# CONNECTOR_A.net
KiCad netlist of a schematic drawn in Altium Designer
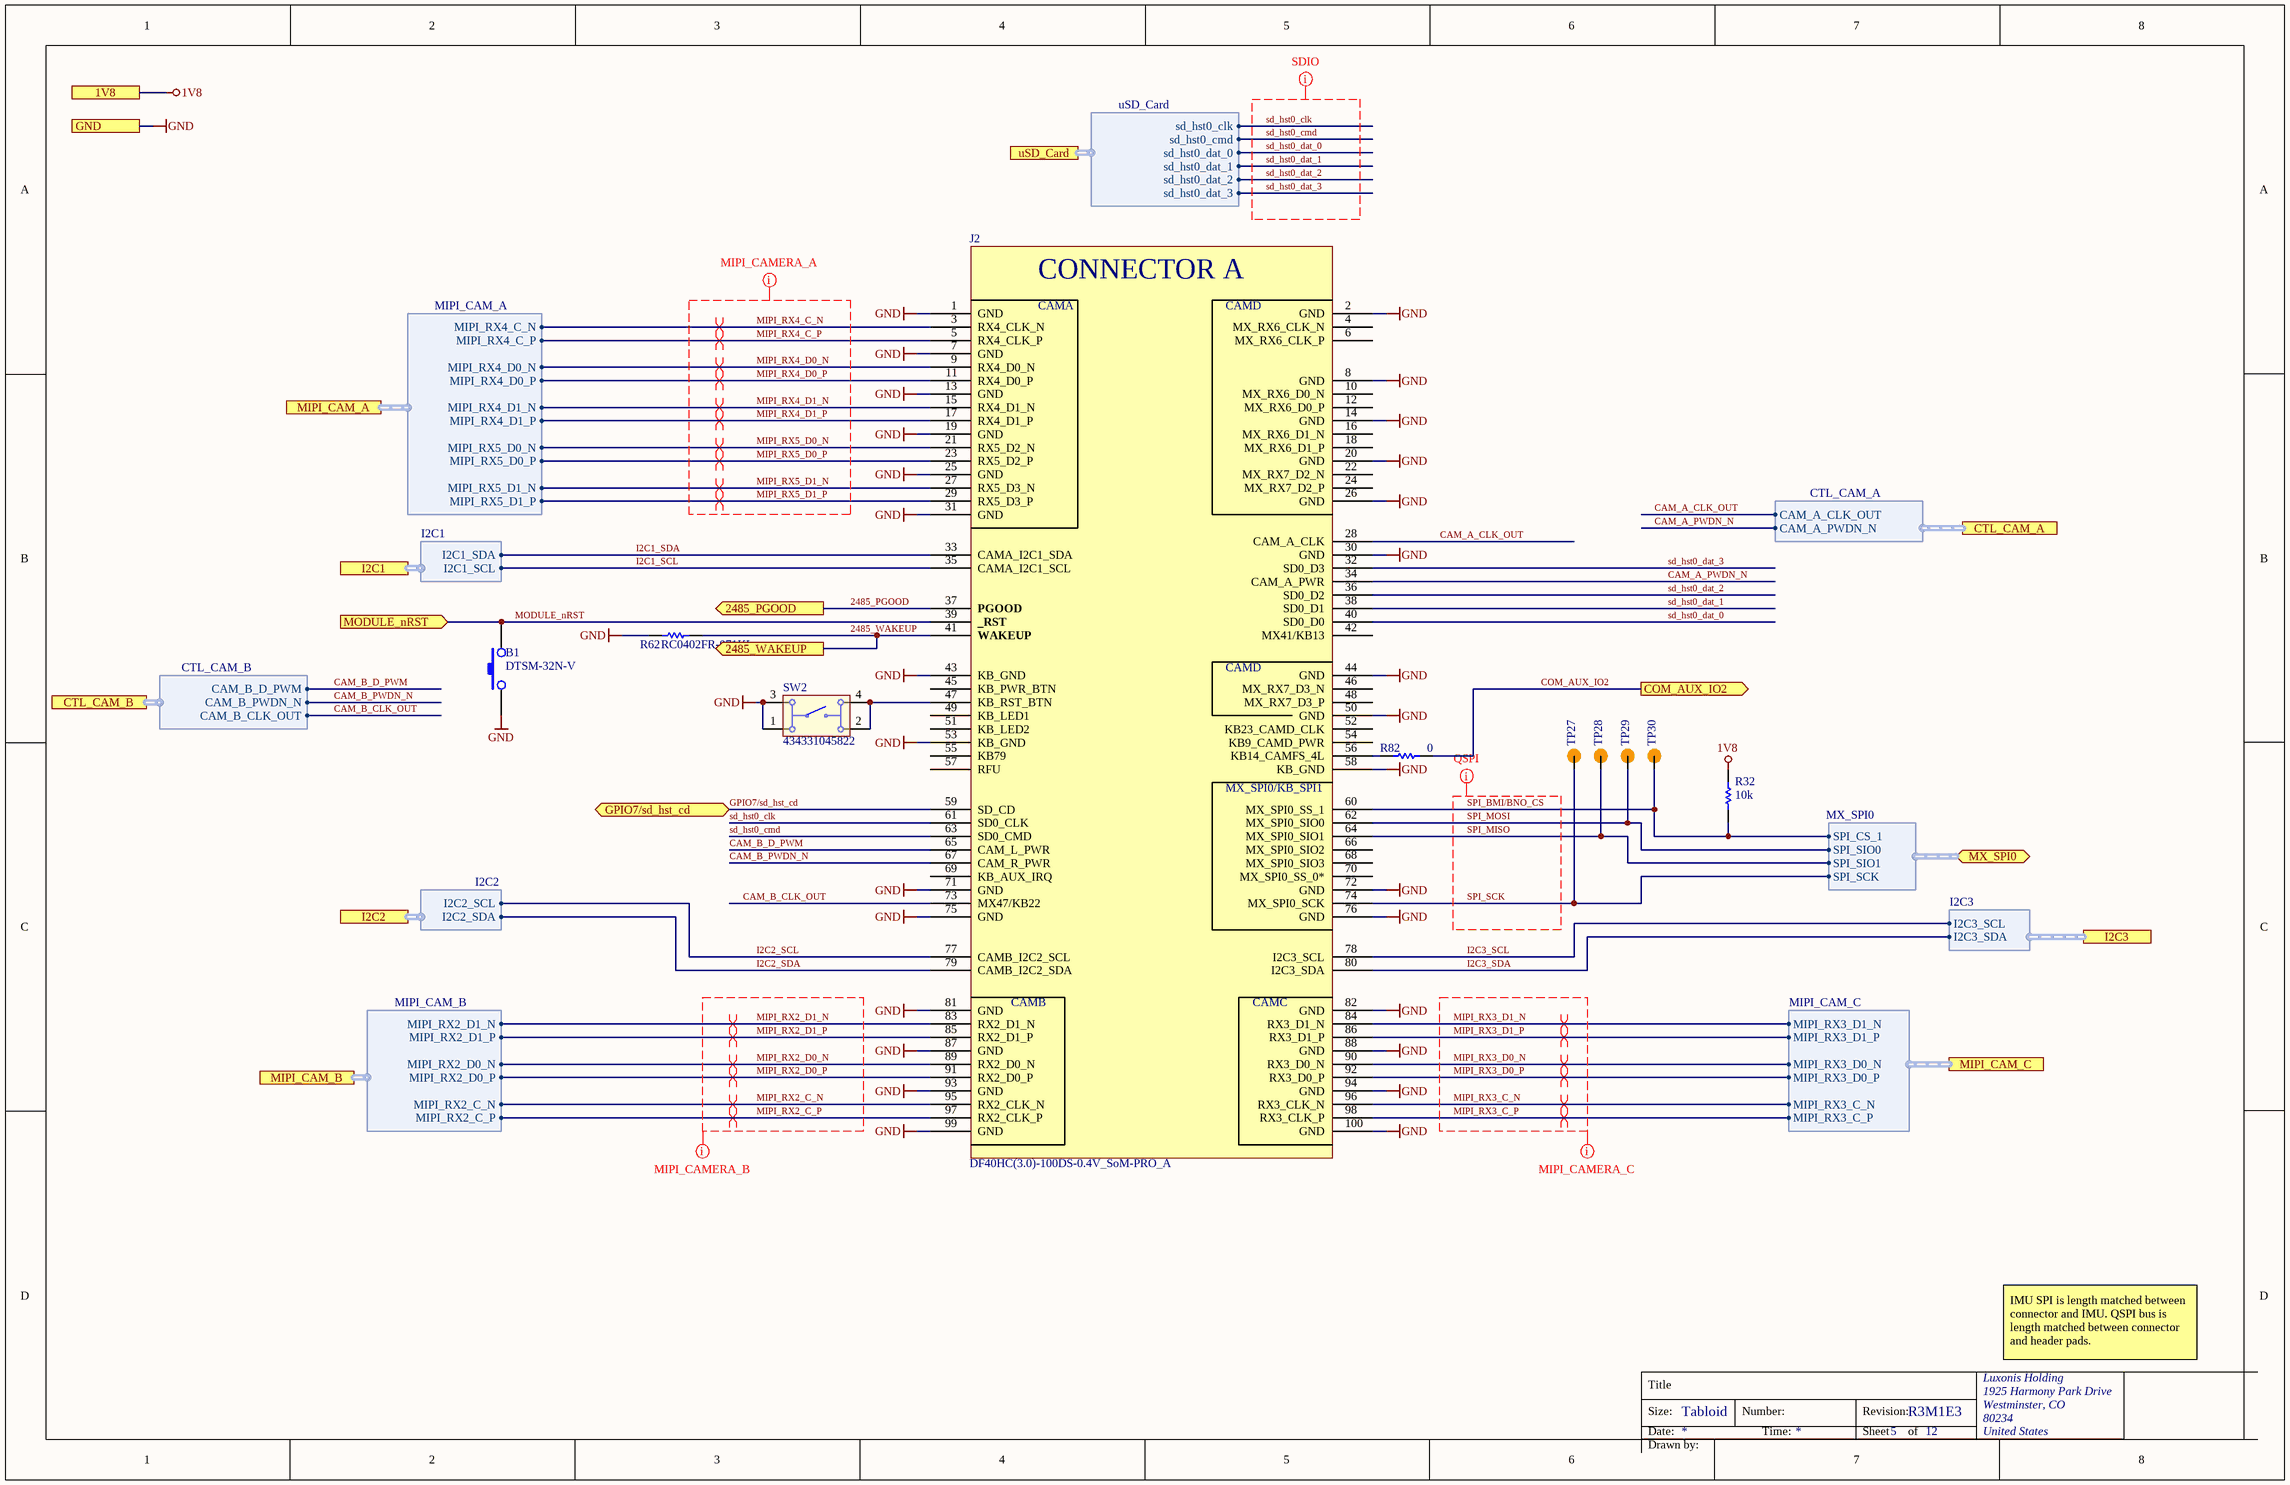
[diagram p0: CONNECTOR_A.SchDoc]

(export (version "E")
  (design (tool "Eeschema 10.0.6"))
  (components
    (comp (ref "B1")
      (value "DTSM-32N-V")
      (footprint "DTSM-32N-V")
      (description "SWITCH TACTILE SMT 3.5mm * 6mm , brown 160gf")
      (libsource (lib "Luxonis LLC") (part "DTSM-32N-V"))
    )
    (comp (ref "J2")
      (value "DF40HC(3.0)-100DS-0.4V_SoM-PRO_A")
      (footprint "CON_A_BW2099_SoM_DF40HC-3.0-100DS-0.4V_minpad")
      (description "OAK-SoM-Pro_S2/S3 base board conn. A")
      (libsource (lib "Luxonis LLC") (part "DF40HC(3.0)-100DS-0.4V_SoM-PRO_A"))
    )
    (comp (ref "R32")
      (value "10k")
      (footprint "RESC0402(1005)_L")
      (description "RES SMD 10K OHM 1% 1/16W 0402")
      (fields (field (name "TOLERANCE") "1%") (field (name "Comment") "RC0402FR-1310KL"))
      (libsource (lib "Luxonis LLC") (part "RC0402FR-0722RL_1"))
    )
    (comp (ref "R62")
      (value "RC0402FR-071KL")
      (footprint "RESC0402(1005)_L")
      (description "RES SMD 1K OHM 1% 1/16W 0402")
      (fields (field (name "TOLERANCE") "1%"))
      (libsource (lib "Luxonis LLC") (part "Default resistor symbol"))
    )
    (comp (ref "R82")
      (value "0")
      (footprint "RESC0402(1005)_L")
      (description "RES SMD 0 OHM 5% 1/16W 0402")
      (fields (field (name "TOLERANCE") "5%") (field (name "Comment") "CRCW04020000Z0ED"))
      (libsource (lib "Luxonis LLC") (part "Default resistor symbol"))
    )
    (comp (ref "SW2")
      (value "434331045822")
      (footprint "434331045822")
      (libsource (lib "Luxonis LLC") (part "WE-TACT-SW-4"))
    )
    (comp (ref "TP27")
      (value "TEST_POINT")
      (footprint "TP100_200_NS")
      (libsource (lib "Luxonis LLC") (part "TEST_POINT"))
    )
    (comp (ref "TP28")
      (value "TEST_POINT")
      (footprint "TP100_200_NS")
      (libsource (lib "Luxonis LLC") (part "TEST_POINT"))
    )
    (comp (ref "TP29")
      (value "TEST_POINT")
      (footprint "TP100_200_NS")
      (libsource (lib "Luxonis LLC") (part "TEST_POINT"))
    )
    (comp (ref "TP30")
      (value "TEST_POINT")
      (footprint "TP100_200_NS")
      (libsource (lib "Luxonis LLC") (part "TEST_POINT"))
    )
  )
  (nets
    (net (code "11") (name "/2485_PGOOD") (class "Default")
      (node (ref "J2") (pin "37") (pinfunction "PGOOD_37") (pintype "passive"))
    )
    (net (code "12") (name "/2485_WAKEUP") (class "Default")
      (node (ref "J2") (pin "41") (pinfunction "WAKEUP_41") (pintype "passive"))
      (node (ref "R62") (pin "1") (pinfunction "1_1") (pintype "passive"))
    )
    (net (code "13") (name "/CAM_A_CLK_OUT") (class "Default")
      (node (ref "J2") (pin "28") (pinfunction "CAM_A_CLK_28") (pintype "passive"))
    )
    (net (code "14") (name "/CAM_A_PWDN_N") (class "Default")
      (node (ref "J2") (pin "34") (pinfunction "CAM_A_PWR_34") (pintype "passive"))
    )
    (net (code "15") (name "/CAM_B_CLK_OUT") (class "Default")
      (node (ref "J2") (pin "73") (pinfunction "MX47/KB22_73") (pintype "passive"))
    )
    (net (code "16") (name "/CAM_B_D_PWM") (class "Default")
      (node (ref "J2") (pin "65") (pinfunction "CAM_L_PWR_65") (pintype "passive"))
    )
    (net (code "17") (name "/CAM_B_PWDN_N") (class "Default")
      (node (ref "J2") (pin "67") (pinfunction "CAM_R_PWR_67") (pintype "passive"))
    )
    (net (code "18") (name "/COM_AUX_IO2") (class "Default")
      (node (ref "R82") (pin "1") (pinfunction "1_1") (pintype "passive"))
    )
    (net (code "19") (name "/GPIO7{slash}sd_hst_cd") (class "Default")
      (node (ref "J2") (pin "59") (pinfunction "SD_CD_59") (pintype "passive"))
    )
    (net (code "20") (name "/I2C1_SCL") (class "Default")
      (node (ref "J2") (pin "35") (pinfunction "CAMA_I2C1_SCL_35") (pintype "passive"))
    )
    (net (code "21") (name "/I2C1_SDA") (class "Default")
      (node (ref "J2") (pin "33") (pinfunction "CAMA_I2C1_SDA_33") (pintype "passive"))
    )
    (net (code "22") (name "/I2C2_SCL") (class "Default")
      (node (ref "J2") (pin "77") (pinfunction "CAMB_I2C2_SCL_77") (pintype "passive"))
    )
    (net (code "23") (name "/I2C2_SDA") (class "Default")
      (node (ref "J2") (pin "79") (pinfunction "CAMB_I2C2_SDA_79") (pintype "passive"))
    )
    (net (code "24") (name "/I2C3_SCL") (class "Default")
      (node (ref "J2") (pin "78") (pinfunction "I2C3_SCL_78") (pintype "passive"))
    )
    (net (code "25") (name "/I2C3_SDA") (class "Default")
      (node (ref "J2") (pin "80") (pinfunction "I2C3_SDA_80") (pintype "passive"))
    )
    (net (code "26") (name "/MIPI_RX2_C_N") (class "Default")
      (node (ref "J2") (pin "95") (pinfunction "RX2_CLK_N_95") (pintype "passive"))
    )
    (net (code "27") (name "/MIPI_RX2_C_P") (class "Default")
      (node (ref "J2") (pin "97") (pinfunction "RX2_CLK_P_97") (pintype "passive"))
    )
    (net (code "28") (name "/MIPI_RX2_D0_N") (class "Default")
      (node (ref "J2") (pin "89") (pinfunction "RX2_D0_N_89") (pintype "passive"))
    )
    (net (code "29") (name "/MIPI_RX2_D0_P") (class "Default")
      (node (ref "J2") (pin "91") (pinfunction "RX2_D0_P_91") (pintype "passive"))
    )
    (net (code "30") (name "/MIPI_RX2_D1_N") (class "Default")
      (node (ref "J2") (pin "83") (pinfunction "RX2_D1_N_83") (pintype "passive"))
    )
    (net (code "31") (name "/MIPI_RX2_D1_P") (class "Default")
      (node (ref "J2") (pin "85") (pinfunction "RX2_D1_P_85") (pintype "passive"))
    )
    (net (code "32") (name "/MIPI_RX3_C_N") (class "Default")
      (node (ref "J2") (pin "96") (pinfunction "RX3_CLK_N_96") (pintype "passive"))
    )
    (net (code "33") (name "/MIPI_RX3_C_P") (class "Default")
      (node (ref "J2") (pin "98") (pinfunction "RX3_CLK_P_98") (pintype "passive"))
    )
    (net (code "34") (name "/MIPI_RX3_D0_N") (class "Default")
      (node (ref "J2") (pin "90") (pinfunction "RX3_D0_N_90") (pintype "passive"))
    )
    (net (code "35") (name "/MIPI_RX3_D0_P") (class "Default")
      (node (ref "J2") (pin "92") (pinfunction "RX3_D0_P_92") (pintype "passive"))
    )
    (net (code "36") (name "/MIPI_RX3_D1_N") (class "Default")
      (node (ref "J2") (pin "84") (pinfunction "RX3_D1_N_84") (pintype "passive"))
    )
    (net (code "37") (name "/MIPI_RX3_D1_P") (class "Default")
      (node (ref "J2") (pin "86") (pinfunction "RX3_D1_P_86") (pintype "passive"))
    )
    (net (code "38") (name "/MIPI_RX4_C_N") (class "Default")
      (node (ref "J2") (pin "3") (pinfunction "RX4_CLK_N_3") (pintype "passive"))
    )
    (net (code "39") (name "/MIPI_RX4_C_P") (class "Default")
      (node (ref "J2") (pin "5") (pinfunction "RX4_CLK_P_5") (pintype "passive"))
    )
    (net (code "40") (name "/MIPI_RX4_D0_N") (class "Default")
      (node (ref "J2") (pin "9") (pinfunction "RX4_D0_N_9") (pintype "passive"))
    )
    (net (code "41") (name "/MIPI_RX4_D0_P") (class "Default")
      (node (ref "J2") (pin "11") (pinfunction "RX4_D0_P_11") (pintype "passive"))
    )
    (net (code "42") (name "/MIPI_RX4_D1_N") (class "Default")
      (node (ref "J2") (pin "15") (pinfunction "RX4_D1_N_15") (pintype "passive"))
    )
    (net (code "43") (name "/MIPI_RX4_D1_P") (class "Default")
      (node (ref "J2") (pin "17") (pinfunction "RX4_D1_P_17") (pintype "passive"))
    )
    (net (code "44") (name "/MIPI_RX5_D0_N") (class "Default")
      (node (ref "J2") (pin "21") (pinfunction "RX5_D2_N_21") (pintype "passive"))
    )
    (net (code "45") (name "/MIPI_RX5_D0_P") (class "Default")
      (node (ref "J2") (pin "23") (pinfunction "RX5_D2_P_23") (pintype "passive"))
    )
    (net (code "46") (name "/MIPI_RX5_D1_N") (class "Default")
      (node (ref "J2") (pin "27") (pinfunction "RX5_D3_N_27") (pintype "passive"))
    )
    (net (code "47") (name "/MIPI_RX5_D1_P") (class "Default")
      (node (ref "J2") (pin "29") (pinfunction "RX5_D3_P_29") (pintype "passive"))
    )
    (net (code "48") (name "/MODULE_nRST") (class "Default")
      (node (ref "B1") (pin "2") (pinfunction "2_2") (pintype "passive"))
      (node (ref "J2") (pin "39") (pinfunction "_RST_39") (pintype "passive"))
    )
    (net (code "49") (name "/SPI_BMI{slash}BNO_CS") (class "Default")
      (node (ref "J2") (pin "60") (pinfunction "MX_SPI0_SS_1_60") (pintype "passive"))
      (node (ref "R32") (pin "1") (pinfunction "1_1") (pintype "passive"))
      (node (ref "TP30") (pin "1") (pintype "passive"))
    )
    (net (code "50") (name "/SPI_MISO") (class "Default")
      (node (ref "J2") (pin "64") (pinfunction "MX_SPI0_SIO1_64") (pintype "passive"))
      (node (ref "TP28") (pin "1") (pintype "passive"))
    )
    (net (code "51") (name "/SPI_MOSI") (class "Default")
      (node (ref "J2") (pin "62") (pinfunction "MX_SPI0_SIO0_62") (pintype "passive"))
      (node (ref "TP29") (pin "1") (pintype "passive"))
    )
    (net (code "52") (name "/SPI_SCK") (class "Default")
      (node (ref "J2") (pin "74") (pinfunction "MX_SPI0_SCK_74") (pintype "passive"))
      (node (ref "TP27") (pin "1") (pintype "passive"))
    )
    (net (code "53") (name "/sd_hst0_clk") (class "Default")
      (node (ref "J2") (pin "61") (pinfunction "SD0_CLK_61") (pintype "passive"))
    )
    (net (code "54") (name "/sd_hst0_cmd") (class "Default")
      (node (ref "J2") (pin "63") (pinfunction "SD0_CMD_63") (pintype "passive"))
    )
    (net (code "55") (name "/sd_hst0_dat_0") (class "Default")
      (node (ref "J2") (pin "40") (pinfunction "SD0_D0_40") (pintype "passive"))
    )
    (net (code "56") (name "/sd_hst0_dat_1") (class "Default")
      (node (ref "J2") (pin "38") (pinfunction "SD0_D1_38") (pintype "passive"))
    )
    (net (code "57") (name "/sd_hst0_dat_2") (class "Default")
      (node (ref "J2") (pin "36") (pinfunction "SD0_D2_36") (pintype "passive"))
    )
    (net (code "58") (name "/sd_hst0_dat_3") (class "Default")
      (node (ref "J2") (pin "32") (pinfunction "SD0_D3_32") (pintype "passive"))
    )
    (net (code "69") (name "1V8") (class "Default")
      (node (ref "R32") (pin "2") (pinfunction "2_2") (pintype "passive"))
    )
    (net (code "70") (name "GND") (class "Default")
      (node (ref "B1") (pin "1") (pinfunction "1_1") (pintype "passive"))
      (node (ref "J2") (pin "1") (pinfunction "GND_1") (pintype "passive"))
      (node (ref "J2") (pin "100") (pinfunction "GND_100") (pintype "passive"))
      (node (ref "J2") (pin "13") (pinfunction "GND_13") (pintype "passive"))
      (node (ref "J2") (pin "14") (pinfunction "GND_14") (pintype "passive"))
      (node (ref "J2") (pin "19") (pinfunction "GND_19") (pintype "passive"))
      (node (ref "J2") (pin "2") (pinfunction "GND_2") (pintype "passive"))
      (node (ref "J2") (pin "20") (pinfunction "GND_20") (pintype "passive"))
      (node (ref "J2") (pin "25") (pinfunction "GND_25") (pintype "passive"))
      (node (ref "J2") (pin "26") (pinfunction "GND_26") (pintype "passive"))
      (node (ref "J2") (pin "30") (pinfunction "GND_30") (pintype "passive"))
      (node (ref "J2") (pin "31") (pinfunction "GND_31") (pintype "passive"))
      (node (ref "J2") (pin "43") (pinfunction "KB_GND_43") (pintype "passive"))
      (node (ref "J2") (pin "44") (pinfunction "GND_44") (pintype "passive"))
      (node (ref "J2") (pin "50") (pinfunction "GND_50") (pintype "passive"))
      (node (ref "J2") (pin "53") (pinfunction "KB_GND_53") (pintype "passive"))
      (node (ref "J2") (pin "58") (pinfunction "KB_GND_58") (pintype "passive"))
      (node (ref "J2") (pin "7") (pinfunction "GND_7") (pintype "passive"))
      (node (ref "J2") (pin "71") (pinfunction "GND_71") (pintype "passive"))
      (node (ref "J2") (pin "72") (pinfunction "GND_72") (pintype "passive"))
      (node (ref "J2") (pin "75") (pinfunction "GND_75") (pintype "passive"))
      (node (ref "J2") (pin "76") (pinfunction "GND_76") (pintype "passive"))
      (node (ref "J2") (pin "8") (pinfunction "GND_8") (pintype "passive"))
      (node (ref "J2") (pin "81") (pinfunction "GND_81") (pintype "passive"))
      (node (ref "J2") (pin "82") (pinfunction "GND_82") (pintype "passive"))
      (node (ref "J2") (pin "87") (pinfunction "GND_87") (pintype "passive"))
      (node (ref "J2") (pin "88") (pinfunction "GND_88") (pintype "passive"))
      (node (ref "J2") (pin "93") (pinfunction "GND_93") (pintype "passive"))
      (node (ref "J2") (pin "94") (pinfunction "GND_94") (pintype "passive"))
      (node (ref "J2") (pin "99") (pinfunction "GND_99") (pintype "passive"))
      (node (ref "R62") (pin "2") (pinfunction "2_2") (pintype "passive"))
      (node (ref "SW2") (pin "1") (pinfunction "1_1") (pintype "passive"))
      (node (ref "SW2") (pin "3") (pinfunction "3_3") (pintype "passive"))
    )
    (net (code "71") (name "Net-(J2-KB14_CAMFS_4L)") (class "Default")
      (node (ref "J2") (pin "56") (pinfunction "KB14_CAMFS_4L_56") (pintype "passive"))
      (node (ref "R82") (pin "2") (pinfunction "2_2") (pintype "passive"))
    )
    (net (code "72") (name "Net-(J2-KB_RST_BTN)") (class "Default")
      (node (ref "J2") (pin "47") (pinfunction "KB_RST_BTN_47") (pintype "passive"))
      (node (ref "SW2") (pin "2") (pinfunction "2_2") (pintype "passive"))
      (node (ref "SW2") (pin "4") (pinfunction "4_4") (pintype "passive"))
    )
    (net (code "73") (name "unconnected-(J2-KB9_CAMD_PWR-Pad54)") (class "Default")
      (node (ref "J2") (pin "54") (pinfunction "KB9_CAMD_PWR_54") (pintype "passive"))
    )
    (net (code "74") (name "unconnected-(J2-KB23_CAMD_CLK-Pad52)") (class "Default")
      (node (ref "J2") (pin "52") (pinfunction "KB23_CAMD_CLK_52") (pintype "passive"))
    )
    (net (code "75") (name "unconnected-(J2-KB79-Pad55)") (class "Default")
      (node (ref "J2") (pin "55") (pinfunction "KB79_55") (pintype "passive"))
    )
    (net (code "76") (name "unconnected-(J2-KB_AUX_IRQ-Pad69)") (class "Default")
      (node (ref "J2") (pin "69") (pinfunction "KB_AUX_IRQ_69") (pintype "passive"))
    )
    (net (code "77") (name "unconnected-(J2-KB_LED1-Pad49)") (class "Default")
      (node (ref "J2") (pin "49") (pinfunction "KB_LED1_49") (pintype "passive"))
    )
    (net (code "78") (name "unconnected-(J2-KB_LED2-Pad51)") (class "Default")
      (node (ref "J2") (pin "51") (pinfunction "KB_LED2_51") (pintype "passive"))
    )
    (net (code "79") (name "unconnected-(J2-KB_PWR_BTN-Pad45)") (class "Default")
      (node (ref "J2") (pin "45") (pinfunction "KB_PWR_BTN_45") (pintype "passive"))
    )
    (net (code "80") (name "unconnected-(J2-MX41{slash}KB13-Pad42)") (class "Default")
      (node (ref "J2") (pin "42") (pinfunction "MX41/KB13_42") (pintype "passive"))
    )
    (net (code "81") (name "unconnected-(J2-MX_RX6_CLK_N-Pad4)") (class "Default")
      (node (ref "J2") (pin "4") (pinfunction "MX_RX6_CLK_N_4") (pintype "passive"))
    )
    (net (code "82") (name "unconnected-(J2-MX_RX6_CLK_P-Pad6)") (class "Default")
      (node (ref "J2") (pin "6") (pinfunction "MX_RX6_CLK_P_6") (pintype "passive"))
    )
    (net (code "83") (name "unconnected-(J2-MX_RX6_D0_N-Pad10)") (class "Default")
      (node (ref "J2") (pin "10") (pinfunction "MX_RX6_D0_N_10") (pintype "passive"))
    )
    (net (code "84") (name "unconnected-(J2-MX_RX6_D0_P-Pad12)") (class "Default")
      (node (ref "J2") (pin "12") (pinfunction "MX_RX6_D0_P_12") (pintype "passive"))
    )
    (net (code "85") (name "unconnected-(J2-MX_RX6_D1_N-Pad16)") (class "Default")
      (node (ref "J2") (pin "16") (pinfunction "MX_RX6_D1_N_16") (pintype "passive"))
    )
    (net (code "86") (name "unconnected-(J2-MX_RX6_D1_P-Pad18)") (class "Default")
      (node (ref "J2") (pin "18") (pinfunction "MX_RX6_D1_P_18") (pintype "passive"))
    )
    (net (code "87") (name "unconnected-(J2-MX_RX7_D2_N-Pad22)") (class "Default")
      (node (ref "J2") (pin "22") (pinfunction "MX_RX7_D2_N_22") (pintype "passive"))
    )
    (net (code "88") (name "unconnected-(J2-MX_RX7_D2_P-Pad24)") (class "Default")
      (node (ref "J2") (pin "24") (pinfunction "MX_RX7_D2_P_24") (pintype "passive"))
    )
    (net (code "89") (name "unconnected-(J2-MX_RX7_D3_N-Pad46)") (class "Default")
      (node (ref "J2") (pin "46") (pinfunction "MX_RX7_D3_N_46") (pintype "passive"))
    )
    (net (code "90") (name "unconnected-(J2-MX_RX7_D3_P-Pad48)") (class "Default")
      (node (ref "J2") (pin "48") (pinfunction "MX_RX7_D3_P_48") (pintype "passive"))
    )
    (net (code "91") (name "unconnected-(J2-MX_SPI0_SIO2-Pad66)") (class "Default")
      (node (ref "J2") (pin "66") (pinfunction "MX_SPI0_SIO2_66") (pintype "passive"))
    )
    (net (code "92") (name "unconnected-(J2-MX_SPI0_SIO3-Pad68)") (class "Default")
      (node (ref "J2") (pin "68") (pinfunction "MX_SPI0_SIO3_68") (pintype "passive"))
    )
    (net (code "93") (name "unconnected-(J2-MX_SPI0_SS_0*-Pad70)") (class "Default")
      (node (ref "J2") (pin "70") (pinfunction "MX_SPI0_SS_0*_70") (pintype "passive"))
    )
    (net (code "94") (name "unconnected-(J2-RFU-Pad57)") (class "Default")
      (node (ref "J2") (pin "57") (pinfunction "RFU_57") (pintype "passive"))
    )
  )
)
